# microcontroller.net
KiCad netlist of a schematic drawn in Altium Designer
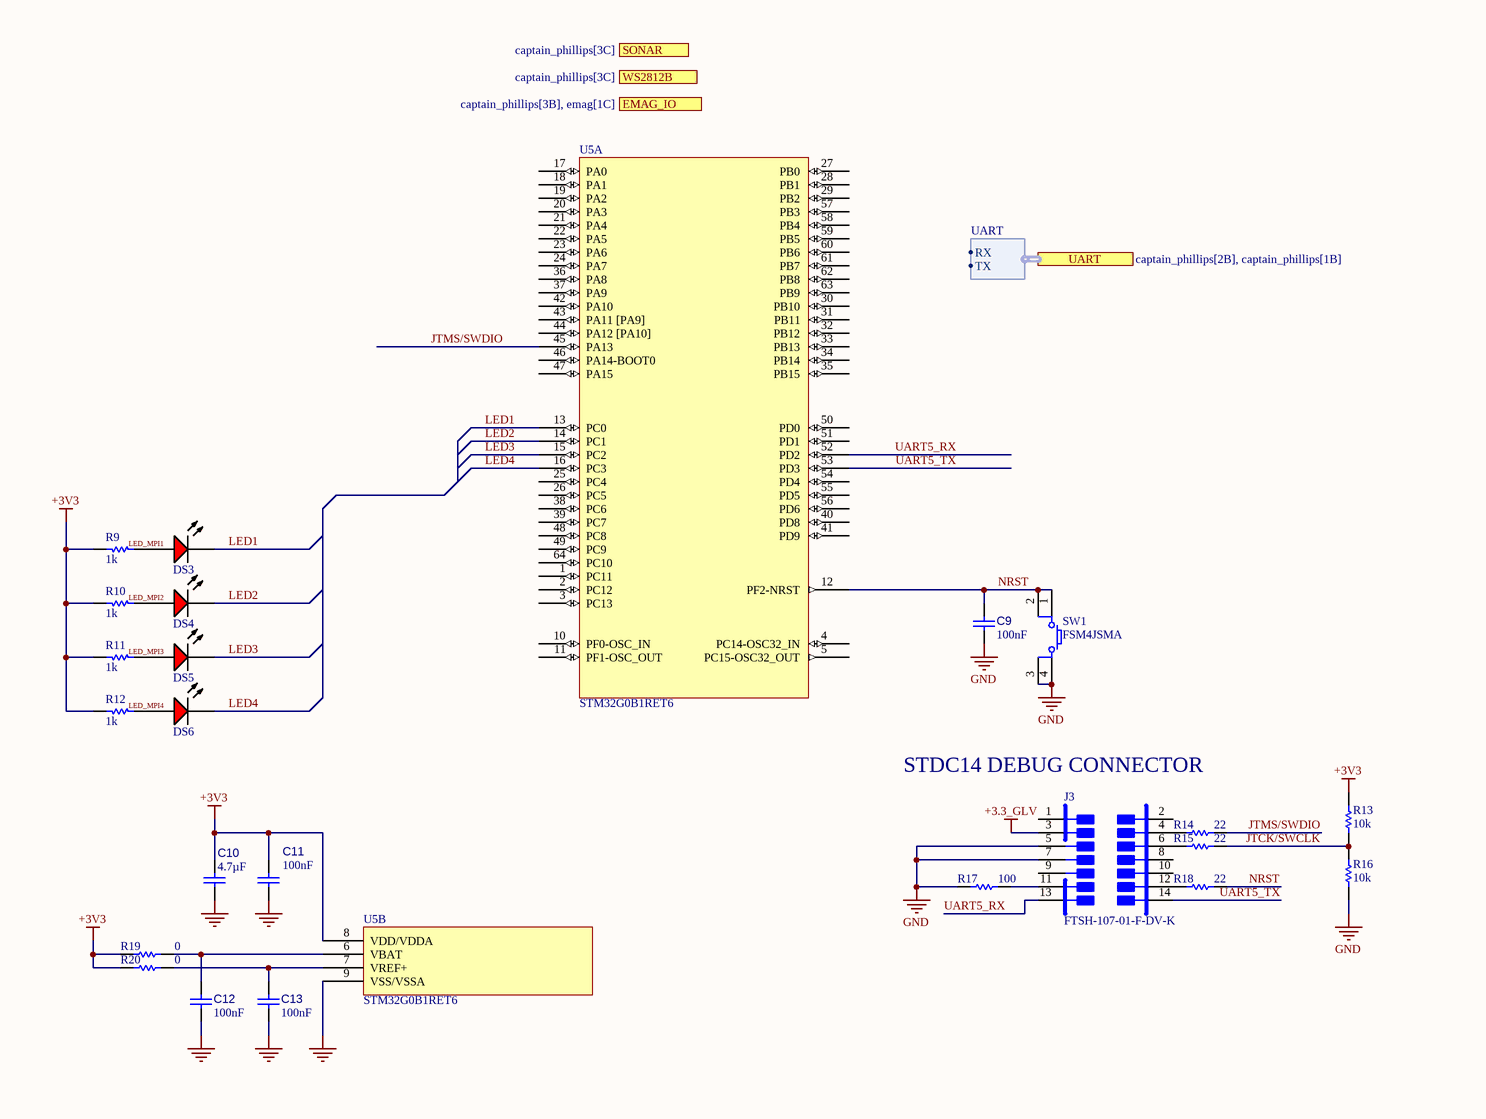
[diagram p0: microcontroller.SchDoc, left]
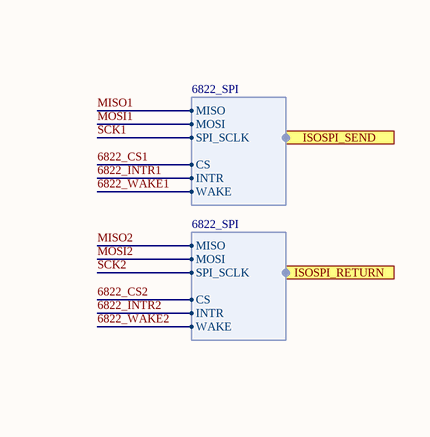
[diagram p1: microcontroller.SchDoc, right]

(export (version "E")
  (design (tool "Eeschema 10.0.6"))
  (components
    (comp (ref "C9")
      (value "100nF")
      (footprint "CAPC1005X05M")
      (description "CAP CER 100nF 25V X7R 0402")
      (fields (field (name "TOLERANCE") "10%") (field (name "LCSC PART NUMBER") "C307331"))
      (libsource (lib "Dalhousie Formula SAE") (part "CAP-NP-2"))
    )
    (comp (ref "C10")
      (value "4.7µF")
      (footprint "CAPC1005X05M")
      (description "CAP CER 4.7uF 10V X7R 0402")
      (fields (field (name "TOLERANCE") "20%") (field (name "LCSC PART NUMBER") "C23733"))
      (libsource (lib "Dalhousie Formula SAE") (part "CAP-NP-2"))
    )
    (comp (ref "C11")
      (value "100nF")
      (footprint "CAPC1005X05M")
      (description "CAP CER 100nF 25V X7R 0402")
      (fields (field (name "TOLERANCE") "10%") (field (name "LCSC PART NUMBER") "C307331"))
      (libsource (lib "Dalhousie Formula SAE") (part "CAP-NP-2"))
    )
    (comp (ref "C12")
      (value "100nF")
      (footprint "CAPC1005X05M")
      (description "CAP CER 100nF 25V X7R 0402")
      (fields (field (name "TOLERANCE") "10%") (field (name "LCSC PART NUMBER") "C307331"))
      (libsource (lib "Dalhousie Formula SAE") (part "CAP-NP-2"))
    )
    (comp (ref "C13")
      (value "100nF")
      (footprint "CAPC1005X05M")
      (description "CAP CER 100nF 25V X7R 0402")
      (fields (field (name "TOLERANCE") "10%") (field (name "LCSC PART NUMBER") "C307331"))
      (libsource (lib "Dalhousie Formula SAE") (part "CAP-NP-2"))
    )
    (comp (ref "DS3")
      (value "19-217/R6C-AL1M2VY/3T")
      (footprint "EVRL-0603-2_V")
      (description "Chip LED, Red, 5 V, 25 mA, -40 to 85 degC, 2-Pin SMD (0603), RoHS, Tape and Reel")
      (fields (field (name "MANUFACTURER") "Everlight Electronics") (field (name "LCSC PART NUMBER") "C2286"))
      (libsource (lib "Dalhousie Formula SAE") (part "LED-RED-AK-2"))
    )
    (comp (ref "DS4")
      (value "19-217/R6C-AL1M2VY/3T")
      (footprint "EVRL-0603-2_V")
      (description "Chip LED, Red, 5 V, 25 mA, -40 to 85 degC, 2-Pin SMD (0603), RoHS, Tape and Reel")
      (fields (field (name "MANUFACTURER") "Everlight Electronics") (field (name "LCSC PART NUMBER") "C2286"))
      (libsource (lib "Dalhousie Formula SAE") (part "LED-RED-AK-2"))
    )
    (comp (ref "DS5")
      (value "19-217/R6C-AL1M2VY/3T")
      (footprint "EVRL-0603-2_V")
      (description "Chip LED, Red, 5 V, 25 mA, -40 to 85 degC, 2-Pin SMD (0603), RoHS, Tape and Reel")
      (fields (field (name "MANUFACTURER") "Everlight Electronics") (field (name "LCSC PART NUMBER") "C2286"))
      (libsource (lib "Dalhousie Formula SAE") (part "LED-RED-AK-2"))
    )
    (comp (ref "DS6")
      (value "19-217/R6C-AL1M2VY/3T")
      (footprint "EVRL-0603-2_V")
      (description "Chip LED, Red, 5 V, 25 mA, -40 to 85 degC, 2-Pin SMD (0603), RoHS, Tape and Reel")
      (fields (field (name "MANUFACTURER") "Everlight Electronics") (field (name "LCSC PART NUMBER") "C2286"))
      (libsource (lib "Dalhousie Formula SAE") (part "LED-RED-AK-2"))
    )
    (comp (ref "J3")
      (value "FTSH-107-01-F-DV-K")
      (footprint "FP-FTSH-107-01-F-DV-K-MFG")
      (fields (field (name "LCSC PART NUMBER") "C7465995"))
      (libsource (lib "Dalhousie Formula SAE") (part "ab214579d66ef07f87fa9c6f4e4f9ab"))
    )
    (comp (ref "R9")
      (value "1k")
      (footprint "RESC1608X55X25ML10T15")
      (description "0603 (1608 Metric) 1/10 W 1K 1% Thick Film Chip Resistor")
      (fields (field (name "POWER") "100mW") (field (name "TOLERANCE") "1%"))
      (libsource (lib "Dalhousie Formula SAE") (part "RES-2"))
    )
    (comp (ref "R10")
      (value "1k")
      (footprint "RESC1608X55X25ML10T15")
      (description "0603 (1608 Metric) 1/10 W 1K 1% Thick Film Chip Resistor")
      (fields (field (name "POWER") "100mW") (field (name "TOLERANCE") "1%"))
      (libsource (lib "Dalhousie Formula SAE") (part "RES-2"))
    )
    (comp (ref "R11")
      (value "1k")
      (footprint "RESC1608X55X25ML10T15")
      (description "0603 (1608 Metric) 1/10 W 1K 1% Thick Film Chip Resistor")
      (fields (field (name "POWER") "100mW") (field (name "TOLERANCE") "1%"))
      (libsource (lib "Dalhousie Formula SAE") (part "RES-2"))
    )
    (comp (ref "R12")
      (value "1k")
      (footprint "RESC1608X55X25ML10T15")
      (description "0603 (1608 Metric) 1/10 W 1K 1% Thick Film Chip Resistor")
      (fields (field (name "POWER") "100mW") (field (name "TOLERANCE") "1%"))
      (libsource (lib "Dalhousie Formula SAE") (part "RES-2"))
    )
    (comp (ref "R13")
      (value "10k")
      (footprint "RESC1608X55X25ML10T15")
      (description "0603 (1608 Metric) 1/10 W 10K 1 Thick Film Chip Resistor")
      (fields (field (name "POWER") "100mW") (field (name "TOLERANCE") "1%"))
      (libsource (lib "Dalhousie Formula SAE") (part "RES-2"))
    )
    (comp (ref "R14")
      (value "22")
      (footprint "RESC1608X55X25ML10T15")
      (description "0603 (1608 Metric) 1/10 W 22R 1 Thick Film Chip Resistor")
      (fields (field (name "TOLERANCE") "1%") (field (name "POWER") "100mW"))
      (libsource (lib "Dalhousie Formula SAE") (part "RES-2"))
    )
    (comp (ref "R15")
      (value "22")
      (footprint "RESC1608X55X25ML10T15")
      (description "0603 (1608 Metric) 1/10 W 22R 1 Thick Film Chip Resistor")
      (fields (field (name "TOLERANCE") "1%") (field (name "POWER") "100mW"))
      (libsource (lib "Dalhousie Formula SAE") (part "RES-2"))
    )
    (comp (ref "R16")
      (value "10k")
      (footprint "RESC1608X55X25ML10T15")
      (description "0603 (1608 Metric) 1/10 W 10K 1 Thick Film Chip Resistor")
      (fields (field (name "POWER") "100mW") (field (name "TOLERANCE") "1%"))
      (libsource (lib "Dalhousie Formula SAE") (part "RES-2"))
    )
    (comp (ref "R17")
      (value "100")
      (footprint "RESC1608X55X25ML10T15")
      (description "0603 (1608 Metric) 1/10 W 100R 1 Thick Film Chip Resistor")
      (fields (field (name "POWER") "100mW") (field (name "TOLERANCE") "1%"))
      (libsource (lib "Dalhousie Formula SAE") (part "RES-2"))
    )
    (comp (ref "R18")
      (value "22")
      (footprint "RESC1608X55X25ML10T15")
      (description "0603 (1608 Metric) 1/10 W 22R 1 Thick Film Chip Resistor")
      (fields (field (name "TOLERANCE") "1%") (field (name "POWER") "100mW"))
      (libsource (lib "Dalhousie Formula SAE") (part "RES-2"))
    )
    (comp (ref "R19")
      (value "0")
      (footprint "RESC1608X55X25ML10T15")
      (description "Jumper 0603 (1608 Metric)")
      (fields (field (name "POWER") "100mW") (field (name "TOLERANCE") "0%"))
      (libsource (lib "Dalhousie Formula SAE") (part "RES-2"))
    )
    (comp (ref "R20")
      (value "0")
      (footprint "RESC1608X55X25ML10T15")
      (description "Jumper 0603 (1608 Metric)")
      (fields (field (name "POWER") "100mW") (field (name "TOLERANCE") "0%"))
      (libsource (lib "Dalhousie Formula SAE") (part "RES-2"))
    )
    (comp (ref "SW1")
      (value "FSM4JSMA")
      (footprint "TECO-FSM4JSMA_V")
      (description "Switch Tactile OFF (ON) SPST Round Button Gull Wing 0.05A 12VDC 1.57N SMD Loose Piece")
      (libsource (lib "Dalhousie Formula SAE") (part "SW-SPST-4_A"))
    )
    (comp (ref "U5")
      (value "STM32G0B1RET6")
      (footprint "STM32G0B1RET6-Footprint-1")
      (description "RISC Microcontroller, 32-Bit, FLASH, Cortex-M0+ CPU, 64MHz, CMOS, PQFP64")
      (fields (field (name "LCSC PART NUMBER") "C2829307"))
      (libsource (lib "Dalhousie Formula SAE") (part "STM32G0B1RET6-Symbol-1"))
    )
  )
  (nets
    (net (code "3") (name "+3.3_GLV") (class "Default")
      (node (ref "J3") (pin "3") (pinfunction "3_3") (pintype "passive"))
    )
    (net (code "4") (name "+3V3") (class "Default")
      (node (ref "C10") (pin "2") (pinfunction "2_2") (pintype "passive"))
      (node (ref "C11") (pin "1") (pinfunction "1_1") (pintype "passive"))
      (node (ref "R10") (pin "2") (pinfunction "2_2") (pintype "passive"))
      (node (ref "R11") (pin "2") (pinfunction "2_2") (pintype "passive"))
      (node (ref "R12") (pin "2") (pinfunction "2_2") (pintype "passive"))
      (node (ref "R13") (pin "2") (pinfunction "2_2") (pintype "passive"))
      (node (ref "R19") (pin "1") (pinfunction "1_1") (pintype "passive"))
      (node (ref "R20") (pin "1") (pinfunction "1_1") (pintype "passive"))
      (node (ref "R9") (pin "2") (pinfunction "2_2") (pintype "passive"))
      (node (ref "U5") (pin "8") (pinfunction "VDD/VDDA_8") (pintype "power_in"))
    )
    (net (code "12") (name "/JTCK{slash}SWCLK") (class "Default")
      (node (ref "R13") (pin "1") (pinfunction "1_1") (pintype "passive"))
      (node (ref "R15") (pin "2") (pinfunction "2_2") (pintype "passive"))
      (node (ref "R16") (pin "2") (pinfunction "2_2") (pintype "passive"))
    )
    (net (code "13") (name "/JTMS{slash}SWDIO") (class "Default")
      (node (ref "R14") (pin "2") (pinfunction "2_2") (pintype "passive"))
      (node (ref "U5") (pin "45") (pinfunction "PA13_45") (pintype "bidirectional"))
    )
    (net (code "14") (name "/LED1") (class "Default")
      (node (ref "DS3") (pin "2") (pinfunction "K_2") (pintype "passive"))
      (node (ref "U5") (pin "13") (pinfunction "PC0_13") (pintype "bidirectional"))
    )
    (net (code "15") (name "/LED2") (class "Default")
      (node (ref "DS4") (pin "2") (pinfunction "K_2") (pintype "passive"))
      (node (ref "U5") (pin "14") (pinfunction "PC1_14") (pintype "bidirectional"))
    )
    (net (code "16") (name "/LED3") (class "Default")
      (node (ref "DS5") (pin "2") (pinfunction "K_2") (pintype "passive"))
      (node (ref "U5") (pin "15") (pinfunction "PC2_15") (pintype "bidirectional"))
    )
    (net (code "17") (name "/LED4") (class "Default")
      (node (ref "DS6") (pin "2") (pinfunction "K_2") (pintype "passive"))
      (node (ref "U5") (pin "16") (pinfunction "PC3_16") (pintype "bidirectional"))
    )
    (net (code "18") (name "/LED_MPI1") (class "Default")
      (node (ref "DS3") (pin "1") (pinfunction "A_1") (pintype "passive"))
      (node (ref "R9") (pin "1") (pinfunction "1_1") (pintype "passive"))
    )
    (net (code "19") (name "/LED_MPI2") (class "Default")
      (node (ref "DS4") (pin "1") (pinfunction "A_1") (pintype "passive"))
      (node (ref "R10") (pin "1") (pinfunction "1_1") (pintype "passive"))
    )
    (net (code "20") (name "/LED_MPI3") (class "Default")
      (node (ref "DS5") (pin "1") (pinfunction "A_1") (pintype "passive"))
      (node (ref "R11") (pin "1") (pinfunction "1_1") (pintype "passive"))
    )
    (net (code "21") (name "/LED_MPI4") (class "Default")
      (node (ref "DS6") (pin "1") (pinfunction "A_1") (pintype "passive"))
      (node (ref "R12") (pin "1") (pinfunction "1_1") (pintype "passive"))
    )
    (net (code "26") (name "/NRST") (class "Default")
      (node (ref "C9") (pin "2") (pinfunction "2_2") (pintype "passive"))
      (node (ref "R18") (pin "2") (pinfunction "2_2") (pintype "passive"))
      (node (ref "SW1") (pin "1") (pinfunction "1_1") (pintype "passive"))
      (node (ref "SW1") (pin "2") (pinfunction "2_2") (pintype "passive"))
      (node (ref "U5") (pin "12") (pinfunction "PF2-NRST_12") (pintype "output"))
    )
    (net (code "30") (name "/UART5_RX") (class "Default")
      (node (ref "J3") (pin "13") (pinfunction "13_13") (pintype "passive"))
      (node (ref "U5") (pin "52") (pinfunction "PD2_52") (pintype "bidirectional"))
    )
    (net (code "31") (name "/UART5_TX") (class "Default")
      (node (ref "J3") (pin "14") (pinfunction "14_14") (pintype "passive"))
      (node (ref "U5") (pin "53") (pinfunction "PD3_53") (pintype "bidirectional"))
    )
    (net (code "35") (name "GND") (class "Default")
      (node (ref "C10") (pin "1") (pinfunction "1_1") (pintype "passive"))
      (node (ref "C11") (pin "2") (pinfunction "2_2") (pintype "passive"))
      (node (ref "C12") (pin "2") (pinfunction "2_2") (pintype "passive"))
      (node (ref "C13") (pin "2") (pinfunction "2_2") (pintype "passive"))
      (node (ref "C9") (pin "1") (pinfunction "1_1") (pintype "passive"))
      (node (ref "J3") (pin "5") (pinfunction "5_5") (pintype "passive"))
      (node (ref "J3") (pin "7") (pinfunction "7_7") (pintype "passive"))
      (node (ref "R16") (pin "1") (pinfunction "1_1") (pintype "passive"))
      (node (ref "R17") (pin "1") (pinfunction "1_1") (pintype "passive"))
      (node (ref "SW1") (pin "3") (pinfunction "3_3") (pintype "passive"))
      (node (ref "SW1") (pin "4") (pinfunction "4_4") (pintype "passive"))
      (node (ref "U5") (pin "9") (pinfunction "VSS/VSSA_9") (pintype "power_in"))
    )
    (net (code "36") (name "Net-(J3-Pad4)") (class "Default")
      (node (ref "J3") (pin "4") (pinfunction "4_4") (pintype "passive"))
      (node (ref "R14") (pin "1") (pinfunction "1_1") (pintype "passive"))
    )
    (net (code "37") (name "Net-(J3-Pad6)") (class "Default")
      (node (ref "J3") (pin "6") (pinfunction "6_6") (pintype "passive"))
      (node (ref "R15") (pin "1") (pinfunction "1_1") (pintype "passive"))
    )
    (net (code "38") (name "Net-(J3-Pad11)") (class "Default")
      (node (ref "J3") (pin "11") (pinfunction "11_11") (pintype "passive"))
      (node (ref "R17") (pin "2") (pinfunction "2_2") (pintype "passive"))
    )
    (net (code "39") (name "Net-(J3-Pad12)") (class "Default")
      (node (ref "J3") (pin "12") (pinfunction "12_12") (pintype "passive"))
      (node (ref "R18") (pin "1") (pinfunction "1_1") (pintype "passive"))
    )
    (net (code "40") (name "Net-(U5B-VBAT)") (class "Default")
      (node (ref "C12") (pin "1") (pinfunction "1_1") (pintype "passive"))
      (node (ref "R19") (pin "2") (pinfunction "2_2") (pintype "passive"))
      (node (ref "U5") (pin "6") (pinfunction "VBAT_6") (pintype "passive"))
    )
    (net (code "41") (name "Net-(U5B-VREF+)") (class "Default")
      (node (ref "C13") (pin "1") (pinfunction "1_1") (pintype "passive"))
      (node (ref "R20") (pin "2") (pinfunction "2_2") (pintype "passive"))
      (node (ref "U5") (pin "7") (pinfunction "VREF+_7") (pintype "power_in"))
    )
    (net (code "42") (name "unconnected-(J3-Pad1)") (class "Default")
      (node (ref "J3") (pin "1") (pinfunction "1_1") (pintype "passive"))
    )
    (net (code "43") (name "unconnected-(J3-Pad2)") (class "Default")
      (node (ref "J3") (pin "2") (pinfunction "2_2") (pintype "passive"))
    )
    (net (code "44") (name "unconnected-(J3-Pad8)") (class "Default")
      (node (ref "J3") (pin "8") (pinfunction "8_8") (pintype "passive"))
    )
    (net (code "45") (name "unconnected-(J3-Pad9)") (class "Default")
      (node (ref "J3") (pin "9") (pinfunction "9_9") (pintype "passive"))
    )
    (net (code "46") (name "unconnected-(J3-Pad10)") (class "Default")
      (node (ref "J3") (pin "10") (pinfunction "10_10") (pintype "passive"))
    )
    (net (code "47") (name "unconnected-(U5A-PA0-Pad17)") (class "Default")
      (node (ref "U5") (pin "17") (pinfunction "PA0_17") (pintype "bidirectional"))
    )
    (net (code "48") (name "unconnected-(U5A-PA1-Pad18)") (class "Default")
      (node (ref "U5") (pin "18") (pinfunction "PA1_18") (pintype "bidirectional"))
    )
    (net (code "49") (name "unconnected-(U5A-PA2-Pad19)") (class "Default")
      (node (ref "U5") (pin "19") (pinfunction "PA2_19") (pintype "bidirectional"))
    )
    (net (code "50") (name "unconnected-(U5A-PA3-Pad20)") (class "Default")
      (node (ref "U5") (pin "20") (pinfunction "PA3_20") (pintype "bidirectional"))
    )
    (net (code "51") (name "unconnected-(U5A-PA4-Pad21)") (class "Default")
      (node (ref "U5") (pin "21") (pinfunction "PA4_21") (pintype "bidirectional"))
    )
    (net (code "52") (name "unconnected-(U5A-PA5-Pad22)") (class "Default")
      (node (ref "U5") (pin "22") (pinfunction "PA5_22") (pintype "bidirectional"))
    )
    (net (code "53") (name "unconnected-(U5A-PA6-Pad23)") (class "Default")
      (node (ref "U5") (pin "23") (pinfunction "PA6_23") (pintype "bidirectional"))
    )
    (net (code "54") (name "unconnected-(U5A-PA7-Pad24)") (class "Default")
      (node (ref "U5") (pin "24") (pinfunction "PA7_24") (pintype "bidirectional"))
    )
    (net (code "55") (name "unconnected-(U5A-PA8-Pad36)") (class "Default")
      (node (ref "U5") (pin "36") (pinfunction "PA8_36") (pintype "bidirectional"))
    )
    (net (code "56") (name "unconnected-(U5A-PA9-Pad37)") (class "Default")
      (node (ref "U5") (pin "37") (pinfunction "PA9_37") (pintype "bidirectional"))
    )
    (net (code "57") (name "unconnected-(U5A-PA10-Pad42)") (class "Default")
      (node (ref "U5") (pin "42") (pinfunction "PA10_42") (pintype "bidirectional"))
    )
    (net (code "58") (name "unconnected-(U5A-PA11_[PA9]-Pad43)") (class "Default")
      (node (ref "U5") (pin "43") (pinfunction "PA11_[PA9]_43") (pintype "bidirectional"))
    )
    (net (code "59") (name "unconnected-(U5A-PA12_[PA10]-Pad44)") (class "Default")
      (node (ref "U5") (pin "44") (pinfunction "PA12_[PA10]_44") (pintype "bidirectional"))
    )
    (net (code "60") (name "unconnected-(U5A-PA14-BOOT0-Pad46)") (class "Default")
      (node (ref "U5") (pin "46") (pinfunction "PA14-BOOT0_46") (pintype "bidirectional"))
    )
    (net (code "61") (name "unconnected-(U5A-PA15-Pad47)") (class "Default")
      (node (ref "U5") (pin "47") (pinfunction "PA15_47") (pintype "bidirectional"))
    )
    (net (code "62") (name "unconnected-(U5A-PB0-Pad27)") (class "Default")
      (node (ref "U5") (pin "27") (pinfunction "PB0_27") (pintype "bidirectional"))
    )
    (net (code "63") (name "unconnected-(U5A-PB1-Pad28)") (class "Default")
      (node (ref "U5") (pin "28") (pinfunction "PB1_28") (pintype "bidirectional"))
    )
    (net (code "64") (name "unconnected-(U5A-PB2-Pad29)") (class "Default")
      (node (ref "U5") (pin "29") (pinfunction "PB2_29") (pintype "bidirectional"))
    )
    (net (code "65") (name "unconnected-(U5A-PB3-Pad57)") (class "Default")
      (node (ref "U5") (pin "57") (pinfunction "PB3_57") (pintype "bidirectional"))
    )
    (net (code "66") (name "unconnected-(U5A-PB4-Pad58)") (class "Default")
      (node (ref "U5") (pin "58") (pinfunction "PB4_58") (pintype "bidirectional"))
    )
    (net (code "67") (name "unconnected-(U5A-PB5-Pad59)") (class "Default")
      (node (ref "U5") (pin "59") (pinfunction "PB5_59") (pintype "bidirectional"))
    )
    (net (code "68") (name "unconnected-(U5A-PB6-Pad60)") (class "Default")
      (node (ref "U5") (pin "60") (pinfunction "PB6_60") (pintype "bidirectional"))
    )
    (net (code "69") (name "unconnected-(U5A-PB7-Pad61)") (class "Default")
      (node (ref "U5") (pin "61") (pinfunction "PB7_61") (pintype "bidirectional"))
    )
    (net (code "70") (name "unconnected-(U5A-PB8-Pad62)") (class "Default")
      (node (ref "U5") (pin "62") (pinfunction "PB8_62") (pintype "bidirectional"))
    )
    (net (code "71") (name "unconnected-(U5A-PB9-Pad63)") (class "Default")
      (node (ref "U5") (pin "63") (pinfunction "PB9_63") (pintype "bidirectional"))
    )
    (net (code "72") (name "unconnected-(U5A-PB10-Pad30)") (class "Default")
      (node (ref "U5") (pin "30") (pinfunction "PB10_30") (pintype "bidirectional"))
    )
    (net (code "73") (name "unconnected-(U5A-PB11-Pad31)") (class "Default")
      (node (ref "U5") (pin "31") (pinfunction "PB11_31") (pintype "bidirectional"))
    )
    (net (code "74") (name "unconnected-(U5A-PB12-Pad32)") (class "Default")
      (node (ref "U5") (pin "32") (pinfunction "PB12_32") (pintype "bidirectional"))
    )
    (net (code "75") (name "unconnected-(U5A-PB13-Pad33)") (class "Default")
      (node (ref "U5") (pin "33") (pinfunction "PB13_33") (pintype "bidirectional"))
    )
    (net (code "76") (name "unconnected-(U5A-PB14-Pad34)") (class "Default")
      (node (ref "U5") (pin "34") (pinfunction "PB14_34") (pintype "bidirectional"))
    )
    (net (code "77") (name "unconnected-(U5A-PB15-Pad35)") (class "Default")
      (node (ref "U5") (pin "35") (pinfunction "PB15_35") (pintype "bidirectional"))
    )
    (net (code "78") (name "unconnected-(U5A-PC4-Pad25)") (class "Default")
      (node (ref "U5") (pin "25") (pinfunction "PC4_25") (pintype "bidirectional"))
    )
    (net (code "79") (name "unconnected-(U5A-PC5-Pad26)") (class "Default")
      (node (ref "U5") (pin "26") (pinfunction "PC5_26") (pintype "bidirectional"))
    )
    (net (code "80") (name "unconnected-(U5A-PC6-Pad38)") (class "Default")
      (node (ref "U5") (pin "38") (pinfunction "PC6_38") (pintype "bidirectional"))
    )
    (net (code "81") (name "unconnected-(U5A-PC7-Pad39)") (class "Default")
      (node (ref "U5") (pin "39") (pinfunction "PC7_39") (pintype "bidirectional"))
    )
    (net (code "82") (name "unconnected-(U5A-PC8-Pad48)") (class "Default")
      (node (ref "U5") (pin "48") (pinfunction "PC8_48") (pintype "bidirectional"))
    )
    (net (code "83") (name "unconnected-(U5A-PC9-Pad49)") (class "Default")
      (node (ref "U5") (pin "49") (pinfunction "PC9_49") (pintype "bidirectional"))
    )
    (net (code "84") (name "unconnected-(U5A-PC10-Pad64)") (class "Default")
      (node (ref "U5") (pin "64") (pinfunction "PC10_64") (pintype "bidirectional"))
    )
    (net (code "85") (name "unconnected-(U5A-PC11-Pad1)") (class "Default")
      (node (ref "U5") (pin "1") (pinfunction "PC11_1") (pintype "bidirectional"))
    )
    (net (code "86") (name "unconnected-(U5A-PC12-Pad2)") (class "Default")
      (node (ref "U5") (pin "2") (pinfunction "PC12_2") (pintype "bidirectional"))
    )
    (net (code "87") (name "unconnected-(U5A-PC13-Pad3)") (class "Default")
      (node (ref "U5") (pin "3") (pinfunction "PC13_3") (pintype "bidirectional"))
    )
    (net (code "88") (name "unconnected-(U5A-PC14-OSC32_IN-Pad4)") (class "Default")
      (node (ref "U5") (pin "4") (pinfunction "PC14-OSC32_IN_4") (pintype "bidirectional"))
    )
    (net (code "89") (name "unconnected-(U5A-PC15-OSC32_OUT-Pad5)") (class "Default")
      (node (ref "U5") (pin "5") (pinfunction "PC15-OSC32_OUT_5") (pintype "output"))
    )
    (net (code "90") (name "unconnected-(U5A-PD0-Pad50)") (class "Default")
      (node (ref "U5") (pin "50") (pinfunction "PD0_50") (pintype "bidirectional"))
    )
    (net (code "91") (name "unconnected-(U5A-PD1-Pad51)") (class "Default")
      (node (ref "U5") (pin "51") (pinfunction "PD1_51") (pintype "bidirectional"))
    )
    (net (code "92") (name "unconnected-(U5A-PD4-Pad54)") (class "Default")
      (node (ref "U5") (pin "54") (pinfunction "PD4_54") (pintype "bidirectional"))
    )
    (net (code "93") (name "unconnected-(U5A-PD5-Pad55)") (class "Default")
      (node (ref "U5") (pin "55") (pinfunction "PD5_55") (pintype "bidirectional"))
    )
    (net (code "94") (name "unconnected-(U5A-PD6-Pad56)") (class "Default")
      (node (ref "U5") (pin "56") (pinfunction "PD6_56") (pintype "bidirectional"))
    )
    (net (code "95") (name "unconnected-(U5A-PD8-Pad40)") (class "Default")
      (node (ref "U5") (pin "40") (pinfunction "PD8_40") (pintype "bidirectional"))
    )
    (net (code "96") (name "unconnected-(U5A-PD9-Pad41)") (class "Default")
      (node (ref "U5") (pin "41") (pinfunction "PD9_41") (pintype "bidirectional"))
    )
    (net (code "97") (name "unconnected-(U5A-PF0-OSC_IN-Pad10)") (class "Default")
      (node (ref "U5") (pin "10") (pinfunction "PF0-OSC_IN_10") (pintype "bidirectional"))
    )
    (net (code "98") (name "unconnected-(U5A-PF1-OSC_OUT-Pad11)") (class "Default")
      (node (ref "U5") (pin "11") (pinfunction "PF1-OSC_OUT_11") (pintype "bidirectional"))
    )
  )
)
